# HALF_BRIDGE.net
KiCad netlist of a schematic drawn in Altium Designer
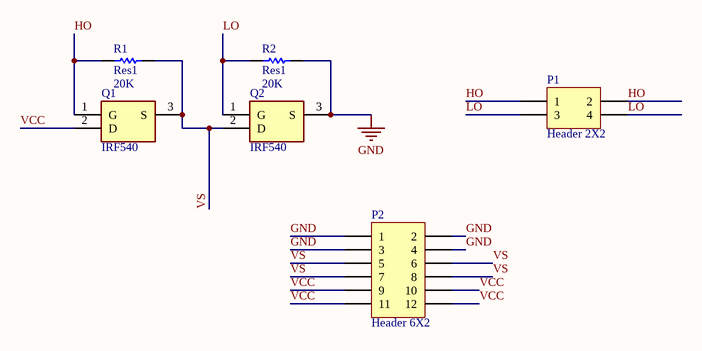
[diagram p0: HALF_BRIDGE.SchDoc]

(export (version "E")
  (design (tool "Eeschema 10.0.6"))
  (components
    (comp (ref "P1")
      (value "Header 2X2")
      (footprint "HDR2X2")
      (description "Header, 2-Pin, Dual row")
      (fields (field (name "PUBLISHER") "Altium Limited"))
      (libsource (lib "Miscellaneous Connectors") (part "Header 2X2"))
    )
    (comp (ref "P2")
      (value "Header 6X2")
      (footprint "HDR2X6")
      (description "Header, 6-Pin, Dual row")
      (fields (field (name "PUBLISHER") "Altium Limited"))
      (libsource (lib "Miscellaneous Connectors") (part "Header 6X2"))
    )
    (comp (ref "Q1")
      (value "IRF540")
      (footprint "SamacSys:TO254P465X1024X2050-3P")
      (description "Transistor")
      (fields (field (name "MOUSER PART NUMBER") "844-IRF540") (field (name "RS PART NUMBER") "3683254"))
      (libsource (lib "*") (part "IRF540"))
    )
    (comp (ref "Q2")
      (value "IRF540")
      (footprint "SamacSys:TO254P465X1024X2050-3P")
      (description "Transistor")
      (fields (field (name "MOUSER PART NUMBER") "844-IRF540") (field (name "RS PART NUMBER") "3683254"))
      (libsource (lib "*") (part "IRF540"))
    )
    (comp (ref "R1")
      (value "Res1")
      (footprint "AXIAL-0.3")
      (description "Resistor")
      (fields (field (name "ALTIUM_VALUE") "20K") (field (name "PUBLISHER") "Altium Limited"))
      (libsource (lib "Miscellaneous Devices") (part "Res1"))
    )
    (comp (ref "R2")
      (value "Res1")
      (footprint "AXIAL-0.3")
      (description "Resistor")
      (fields (field (name "ALTIUM_VALUE") "20K") (field (name "PUBLISHER") "Altium Limited"))
      (libsource (lib "Miscellaneous Devices") (part "Res1"))
    )
  )
  (nets
    (net (code "1") (name "/HO") (class "Default")
      (node (ref "P1") (pin "1") (pinfunction "1_1") (pintype "passive"))
      (node (ref "P1") (pin "2") (pinfunction "2_2") (pintype "passive"))
      (node (ref "Q1") (pin "1") (pinfunction "G_1") (pintype "passive"))
      (node (ref "R1") (pin "1") (pinfunction "1_1") (pintype "passive"))
    )
    (net (code "2") (name "/LO") (class "Default")
      (node (ref "P1") (pin "3") (pinfunction "3_3") (pintype "passive"))
      (node (ref "P1") (pin "4") (pinfunction "4_4") (pintype "passive"))
      (node (ref "Q2") (pin "1") (pinfunction "G_1") (pintype "passive"))
      (node (ref "R2") (pin "1") (pinfunction "1_1") (pintype "passive"))
    )
    (net (code "3") (name "/VCC") (class "Default")
      (node (ref "P2") (pin "10") (pinfunction "10_10") (pintype "passive"))
      (node (ref "P2") (pin "11") (pinfunction "11_11") (pintype "passive"))
      (node (ref "P2") (pin "12") (pinfunction "12_12") (pintype "passive"))
      (node (ref "P2") (pin "9") (pinfunction "9_9") (pintype "passive"))
      (node (ref "Q1") (pin "2") (pinfunction "D_2") (pintype "passive"))
    )
    (net (code "4") (name "/VS") (class "Default")
      (node (ref "P2") (pin "5") (pinfunction "5_5") (pintype "passive"))
      (node (ref "P2") (pin "6") (pinfunction "6_6") (pintype "passive"))
      (node (ref "P2") (pin "7") (pinfunction "7_7") (pintype "passive"))
      (node (ref "P2") (pin "8") (pinfunction "8_8") (pintype "passive"))
      (node (ref "Q1") (pin "3") (pinfunction "S_3") (pintype "passive"))
      (node (ref "Q2") (pin "2") (pinfunction "D_2") (pintype "passive"))
      (node (ref "R1") (pin "2") (pinfunction "2_2") (pintype "passive"))
    )
    (net (code "5") (name "GND") (class "Default")
      (node (ref "P2") (pin "1") (pinfunction "1_1") (pintype "passive"))
      (node (ref "P2") (pin "2") (pinfunction "2_2") (pintype "passive"))
      (node (ref "P2") (pin "3") (pinfunction "3_3") (pintype "passive"))
      (node (ref "P2") (pin "4") (pinfunction "4_4") (pintype "passive"))
      (node (ref "Q2") (pin "3") (pinfunction "S_3") (pintype "passive"))
      (node (ref "R2") (pin "2") (pinfunction "2_2") (pintype "passive"))
    )
  )
)
